# switch.net
KiCad netlist of a schematic drawn in EAGLE
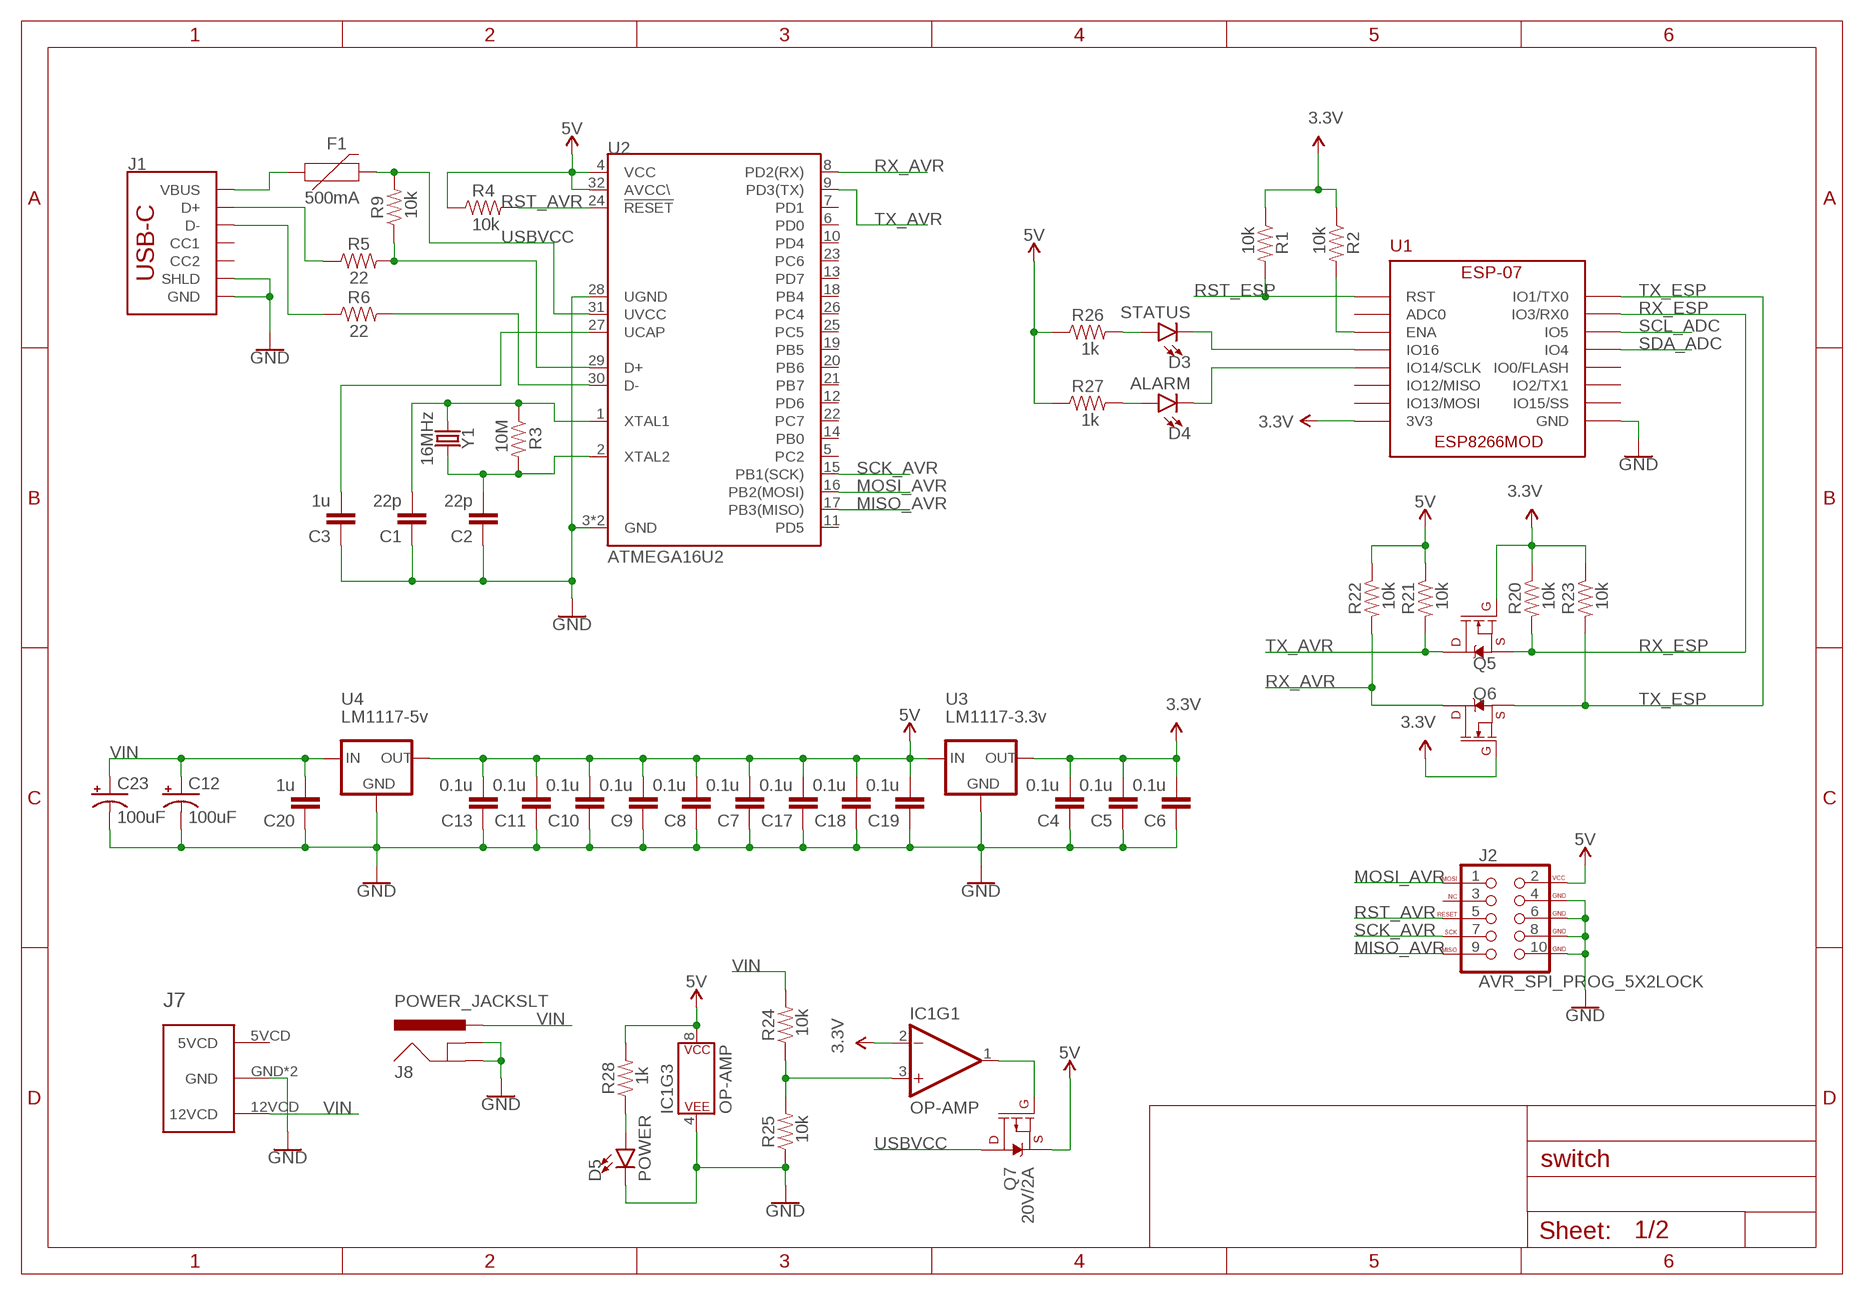
[diagram p0: schematic, sheet 1]
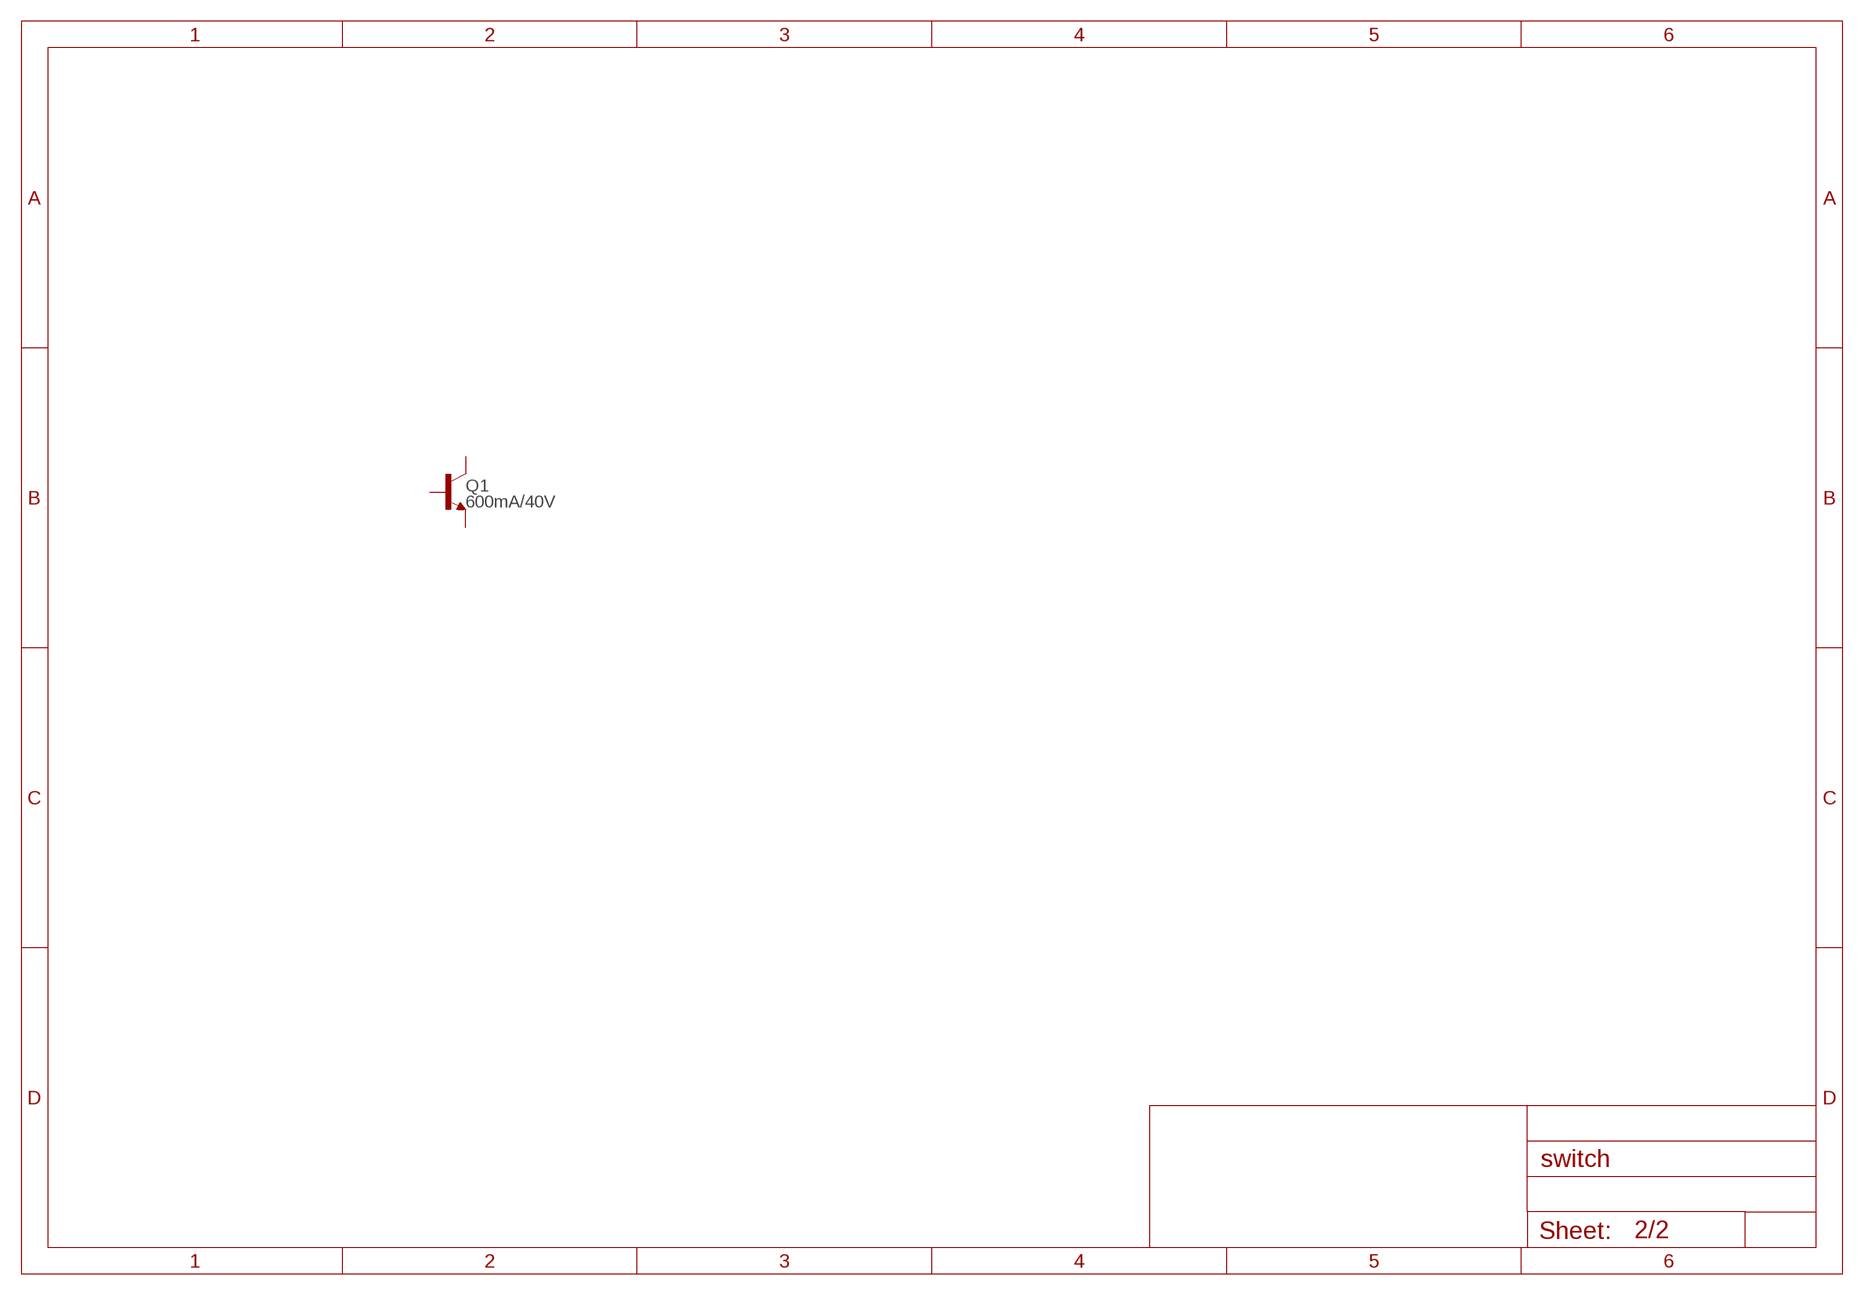
[diagram p1: schematic, sheet 2]

(export (version "E")
  (design (tool "Eeschema 10.0.6"))
  (components
    (comp (ref "C1")
      (value "22p")
      (footprint "eagle-import:0805")
      (libsource (lib "eagle-import") (part "CAP-0805"))
    )
    (comp (ref "C2")
      (value "22p")
      (footprint "eagle-import:0805")
      (libsource (lib "eagle-import") (part "CAP-0805"))
    )
    (comp (ref "C3")
      (value "1u")
      (footprint "eagle-import:0805")
      (libsource (lib "eagle-import") (part "CAP-0805"))
    )
    (comp (ref "C4")
      (value "0.1u")
      (footprint "eagle-import:0805")
      (libsource (lib "eagle-import") (part "CAP-0805"))
    )
    (comp (ref "C5")
      (value "0.1u")
      (footprint "eagle-import:0805")
      (libsource (lib "eagle-import") (part "CAP-0805"))
    )
    (comp (ref "C6")
      (value "0.1u")
      (footprint "eagle-import:0805")
      (libsource (lib "eagle-import") (part "CAP-0805"))
    )
    (comp (ref "C7")
      (value "0.1u")
      (footprint "eagle-import:0805")
      (libsource (lib "eagle-import") (part "CAP-0805"))
    )
    (comp (ref "C8")
      (value "0.1u")
      (footprint "eagle-import:0805")
      (libsource (lib "eagle-import") (part "CAP-0805"))
    )
    (comp (ref "C9")
      (value "0.1u")
      (footprint "eagle-import:0805")
      (libsource (lib "eagle-import") (part "CAP-0805"))
    )
    (comp (ref "C10")
      (value "0.1u")
      (footprint "eagle-import:0805")
      (libsource (lib "eagle-import") (part "CAP-0805"))
    )
    (comp (ref "C11")
      (value "0.1u")
      (footprint "eagle-import:0805")
      (libsource (lib "eagle-import") (part "CAP-0805"))
    )
    (comp (ref "C12")
      (value "100uF")
      (footprint "eagle-import:PANASONIC_D")
      (libsource (lib "eagle-import") (part "100UF-POLAR-25V-20%(ELEC)"))
    )
    (comp (ref "C13")
      (value "0.1u")
      (footprint "eagle-import:0805")
      (libsource (lib "eagle-import") (part "CAP-0805"))
    )
    (comp (ref "C17")
      (value "0.1u")
      (footprint "eagle-import:0805")
      (libsource (lib "eagle-import") (part "CAP-0805"))
    )
    (comp (ref "C18")
      (value "0.1u")
      (footprint "eagle-import:0805")
      (libsource (lib "eagle-import") (part "CAP-0805"))
    )
    (comp (ref "C19")
      (value "0.1u")
      (footprint "eagle-import:0805")
      (libsource (lib "eagle-import") (part "CAP-0805"))
    )
    (comp (ref "C20")
      (value "1u")
      (footprint "eagle-import:0805")
      (libsource (lib "eagle-import") (part "CAP-0805"))
    )
    (comp (ref "C23")
      (value "100uF")
      (footprint "eagle-import:PANASONIC_D")
      (libsource (lib "eagle-import") (part "100UF-POLAR-25V-20%(ELEC)"))
    )
    (comp (ref "D3")
      (value "STATUS")
      (footprint "eagle-import:LED-0603")
      (libsource (lib "eagle-import") (part "LED-YELLOW0603"))
    )
    (comp (ref "D4")
      (value "ALARM")
      (footprint "eagle-import:LED-0603")
      (libsource (lib "eagle-import") (part "LED-YELLOW0603"))
    )
    (comp (ref "D5")
      (value "POWER")
      (footprint "eagle-import:LED-0603")
      (libsource (lib "eagle-import") (part "LED-YELLOW0603"))
    )
    (comp (ref "F1")
      (value "500mA")
      (footprint "eagle-import:1812")
      (libsource (lib "eagle-import") (part "PPTC_16V_2.5A"))
    )
    (comp (ref "IC1")
      (value "OP-AMP")
      (footprint "eagle-import:SO08")
      (libsource (lib "eagle-import") (part "OPAMP-DUALU"))
    )
    (comp (ref "J1")
      (value "USB_C_2-LAYER_PADS")
      (footprint "eagle-import:USB-C-16P-2LAYER-PADS")
      (libsource (lib "eagle-import") (part "USB_C_2-LAYER_PADS"))
    )
    (comp (ref "J2")
      (value "AVR_SPI_PROG_5X2LOCK")
      (footprint "eagle-import:2X5-SHROUDED_LOCK")
      (libsource (lib "eagle-import") (part "AVR_SPI_PROG_5X2LOCK"))
    )
    (comp (ref "J7")
      (value "MOLEX-CPU-POWER")
      (footprint "eagle-import:MOLEX-5.08-4PIN")
      (libsource (lib "eagle-import") (part "MOLEX-CPU-POWER"))
    )
    (comp (ref "J8")
      (value "POWER_JACKSLT")
      (footprint "eagle-import:POWER_JACK_SLOT")
      (libsource (lib "eagle-import") (part "POWER_JACKSLT"))
    )
    (comp (ref "Q5")
      (value "220mA/50V/3.5Ω")
      (footprint "eagle-import:SOT23-3")
      (libsource (lib "eagle-import") (part "MOSFET-NCH-BSS138"))
    )
    (comp (ref "Q6")
      (value "220mA/50V/3.5Ω")
      (footprint "eagle-import:SOT23-3")
      (libsource (lib "eagle-import") (part "MOSFET-NCH-BSS138"))
    )
    (comp (ref "Q7")
      (value "20V/2A")
      (footprint "eagle-import:SOT23-3")
      (libsource (lib "eagle-import") (part "MOSFET_PCH-DMG2305UX-7"))
    )
    (comp (ref "R1")
      (value "10k")
      (footprint "eagle-import:0805")
      (libsource (lib "eagle-import") (part "RESISTOR0805"))
    )
    (comp (ref "R2")
      (value "10k")
      (footprint "eagle-import:0805")
      (libsource (lib "eagle-import") (part "RESISTOR0805"))
    )
    (comp (ref "R3")
      (value "10M")
      (footprint "eagle-import:0805")
      (libsource (lib "eagle-import") (part "RESISTOR0805"))
    )
    (comp (ref "R4")
      (value "10k")
      (footprint "eagle-import:0805")
      (libsource (lib "eagle-import") (part "RESISTOR0805"))
    )
    (comp (ref "R5")
      (value "22")
      (footprint "eagle-import:0805")
      (libsource (lib "eagle-import") (part "RESISTOR0805"))
    )
    (comp (ref "R6")
      (value "22")
      (footprint "eagle-import:0805")
      (libsource (lib "eagle-import") (part "RESISTOR0805"))
    )
    (comp (ref "R9")
      (value "10k")
      (footprint "eagle-import:0805")
      (libsource (lib "eagle-import") (part "RESISTOR0805"))
    )
    (comp (ref "R20")
      (value "10k")
      (footprint "eagle-import:0805")
      (libsource (lib "eagle-import") (part "RESISTOR0805"))
    )
    (comp (ref "R21")
      (value "10k")
      (footprint "eagle-import:0805")
      (libsource (lib "eagle-import") (part "RESISTOR0805"))
    )
    (comp (ref "R22")
      (value "10k")
      (footprint "eagle-import:0805")
      (libsource (lib "eagle-import") (part "RESISTOR0805"))
    )
    (comp (ref "R23")
      (value "10k")
      (footprint "eagle-import:0805")
      (libsource (lib "eagle-import") (part "RESISTOR0805"))
    )
    (comp (ref "R24")
      (value "10k")
      (footprint "eagle-import:0805")
      (libsource (lib "eagle-import") (part "RESISTOR0805"))
    )
    (comp (ref "R25")
      (value "10k")
      (footprint "eagle-import:0805")
      (libsource (lib "eagle-import") (part "RESISTOR0805"))
    )
    (comp (ref "R26")
      (value "1k")
      (footprint "eagle-import:0805")
      (libsource (lib "eagle-import") (part "RESISTOR0805"))
    )
    (comp (ref "R27")
      (value "1k")
      (footprint "eagle-import:0805")
      (libsource (lib "eagle-import") (part "RESISTOR0805"))
    )
    (comp (ref "R28")
      (value "1k")
      (footprint "eagle-import:0805")
      (libsource (lib "eagle-import") (part "RESISTOR0805"))
    )
    (comp (ref "U1")
      (value "ESP-07")
      (footprint "eagle-import:ESP-07")
      (libsource (lib "eagle-import") (part "ESP-07"))
    )
    (comp (ref "U2")
      (value "ATMEGA16U2")
      (footprint "eagle-import:QFN32")
      (libsource (lib "eagle-import") (part "ATMEGA16U2"))
    )
    (comp (ref "U3")
      (value "LM1117-3.3v")
      (footprint "eagle-import:SOT223")
      (libsource (lib "eagle-import") (part "V_REG_LD1117VXXLD1117-SMD"))
    )
    (comp (ref "U4")
      (value "LM1117-5v")
      (footprint "eagle-import:SOT223")
      (libsource (lib "eagle-import") (part "V_REG_LD1117VXXLD1117-SMD"))
    )
    (comp (ref "Y1")
      (value "16MHz")
      (footprint "eagle-import:CRYSTAL-SMD-5X3.2-4PAD")
      (libsource (lib "eagle-import") (part "CRYSTAL-16MHZSMD-5X3.2"))
    )
    (comp (ref "Q1")
      (value "600mA/40V")
      (footprint "eagle-import:SOT23-3")
      (libsource (lib "eagle-import") (part "TRANS_NPN-MMBT2222AL"))
    )
  )
  (nets
    (net (code "1") (name "3.3V") (class "Default")
      (node (ref "C4") (pin "2") (pinfunction "2_2") (pintype "passive"))
      (node (ref "C5") (pin "2") (pinfunction "2_2") (pintype "passive"))
      (node (ref "C6") (pin "2") (pinfunction "2_2") (pintype "passive"))
      (node (ref "IC1") (pin "2") (pinfunction "-IN_2") (pintype "input"))
      (node (ref "Q5") (pin "1") (pinfunction "G_1") (pintype "bidirectional"))
      (node (ref "Q6") (pin "1") (pinfunction "G_1") (pintype "bidirectional"))
      (node (ref "R1") (pin "1") (pinfunction "1_1") (pintype "passive"))
      (node (ref "R2") (pin "1") (pinfunction "1_1") (pintype "passive"))
      (node (ref "R20") (pin "1") (pinfunction "1_1") (pintype "passive"))
      (node (ref "R23") (pin "1") (pinfunction "1_1") (pintype "passive"))
      (node (ref "U1") (pin "3V3") (pinfunction "3V3_3V3") (pintype "power_in"))
      (node (ref "U3") (pin "2") (pinfunction "OUT_2") (pintype "passive"))
    )
    (net (code "2") (name "5V") (class "Default")
      (node (ref "C10") (pin "2") (pinfunction "2_2") (pintype "passive"))
      (node (ref "C11") (pin "2") (pinfunction "2_2") (pintype "passive"))
      (node (ref "C13") (pin "2") (pinfunction "2_2") (pintype "passive"))
      (node (ref "C17") (pin "2") (pinfunction "2_2") (pintype "passive"))
      (node (ref "C18") (pin "2") (pinfunction "2_2") (pintype "passive"))
      (node (ref "C19") (pin "2") (pinfunction "2_2") (pintype "passive"))
      (node (ref "C7") (pin "2") (pinfunction "2_2") (pintype "passive"))
      (node (ref "C8") (pin "2") (pinfunction "2_2") (pintype "passive"))
      (node (ref "C9") (pin "2") (pinfunction "2_2") (pintype "passive"))
      (node (ref "IC1") (pin "8") (pinfunction "P$V+_8") (pintype "bidirectional"))
      (node (ref "J2") (pin "2") (pinfunction "VCC_2") (pintype "power_in"))
      (node (ref "Q7") (pin "2") (pinfunction "S_2") (pintype "bidirectional"))
      (node (ref "R21") (pin "1") (pinfunction "1_1") (pintype "passive"))
      (node (ref "R22") (pin "1") (pinfunction "1_1") (pintype "passive"))
      (node (ref "R26") (pin "1") (pinfunction "1_1") (pintype "passive"))
      (node (ref "R27") (pin "1") (pinfunction "1_1") (pintype "passive"))
      (node (ref "R28") (pin "2") (pinfunction "2_2") (pintype "passive"))
      (node (ref "R4") (pin "1") (pinfunction "1_1") (pintype "passive"))
      (node (ref "U2") (pin "32") (pinfunction "AVCC\\_32") (pintype "bidirectional"))
      (node (ref "U2") (pin "4") (pinfunction "VCC_4") (pintype "bidirectional"))
      (node (ref "U3") (pin "3") (pinfunction "IN_3") (pintype "input"))
      (node (ref "U4") (pin "2") (pinfunction "OUT_2") (pintype "passive"))
    )
    (net (code "3") (name "GND") (class "Default")
      (node (ref "C1") (pin "1") (pinfunction "1_1") (pintype "passive"))
      (node (ref "C10") (pin "1") (pinfunction "1_1") (pintype "passive"))
      (node (ref "C11") (pin "1") (pinfunction "1_1") (pintype "passive"))
      (node (ref "C12") (pin "-") (pinfunction "-_-") (pintype "passive"))
      (node (ref "C13") (pin "1") (pinfunction "1_1") (pintype "passive"))
      (node (ref "C17") (pin "1") (pinfunction "1_1") (pintype "passive"))
      (node (ref "C18") (pin "1") (pinfunction "1_1") (pintype "passive"))
      (node (ref "C19") (pin "1") (pinfunction "1_1") (pintype "passive"))
      (node (ref "C2") (pin "1") (pinfunction "1_1") (pintype "passive"))
      (node (ref "C20") (pin "1") (pinfunction "1_1") (pintype "passive"))
      (node (ref "C23") (pin "-") (pinfunction "-_-") (pintype "passive"))
      (node (ref "C3") (pin "1") (pinfunction "1_1") (pintype "passive"))
      (node (ref "C4") (pin "1") (pinfunction "1_1") (pintype "passive"))
      (node (ref "C5") (pin "1") (pinfunction "1_1") (pintype "passive"))
      (node (ref "C6") (pin "1") (pinfunction "1_1") (pintype "passive"))
      (node (ref "C7") (pin "1") (pinfunction "1_1") (pintype "passive"))
      (node (ref "C8") (pin "1") (pinfunction "1_1") (pintype "passive"))
      (node (ref "C9") (pin "1") (pinfunction "1_1") (pintype "passive"))
      (node (ref "D5") (pin "C") (pinfunction "C_C") (pintype "passive"))
      (node (ref "IC1") (pin "4") (pinfunction "P$V-_4") (pintype "bidirectional"))
      (node (ref "J1") (pin "GND") (pinfunction "GND_GND") (pintype "bidirectional"))
      (node (ref "J1") (pin "GND2") (pinfunction "GND_GND2") (pintype "bidirectional"))
      (node (ref "J1") (pin "SHLD1") (pinfunction "SHLD_SHLD1") (pintype "bidirectional"))
      (node (ref "J1") (pin "SHLD2") (pinfunction "SHLD_SHLD2") (pintype "bidirectional"))
      (node (ref "J1") (pin "SHLD3") (pinfunction "SHLD_SHLD3") (pintype "bidirectional"))
      (node (ref "J1") (pin "SHLD4") (pinfunction "SHLD_SHLD4") (pintype "bidirectional"))
      (node (ref "J2") (pin "10") (pinfunction "GND_10") (pintype "power_in"))
      (node (ref "J2") (pin "4") (pinfunction "GND_4") (pintype "power_in"))
      (node (ref "J2") (pin "6") (pinfunction "GND_6") (pintype "power_in"))
      (node (ref "J2") (pin "8") (pinfunction "GND_8") (pintype "power_in"))
      (node (ref "J7") (pin "GND") (pinfunction "GND_GND") (pintype "bidirectional"))
      (node (ref "J7") (pin "GND2") (pinfunction "GND_GND2") (pintype "bidirectional"))
      (node (ref "J8") (pin "GND@1") (pinfunction "GNDBREAK_GND@1") (pintype "bidirectional"))
      (node (ref "J8") (pin "GND@2") (pinfunction "GND_GND@2") (pintype "bidirectional"))
      (node (ref "R25") (pin "1") (pinfunction "1_1") (pintype "passive"))
      (node (ref "U1") (pin "GND") (pinfunction "GND_GND") (pintype "power_in"))
      (node (ref "U2") (pin "28") (pinfunction "UGND_28") (pintype "bidirectional"))
      (node (ref "U2") (pin "3") (pinfunction "GND_3") (pintype "bidirectional"))
      (node (ref "U2") (pin "EP") (pinfunction "GND_EP") (pintype "bidirectional"))
      (node (ref "U3") (pin "1") (pinfunction "GND_1") (pintype "input"))
      (node (ref "U4") (pin "1") (pinfunction "GND_1") (pintype "input"))
    )
    (net (code "4") (name "MISO_AVR") (class "Default")
      (node (ref "J2") (pin "9") (pinfunction "MISO_9") (pintype "passive"))
      (node (ref "U2") (pin "17") (pinfunction "PB3(MISO)_17") (pintype "bidirectional"))
    )
    (net (code "5") (name "MOSI_AVR") (class "Default")
      (node (ref "J2") (pin "1") (pinfunction "MOSI_1") (pintype "passive"))
      (node (ref "U2") (pin "16") (pinfunction "PB2(MOSI)_16") (pintype "bidirectional"))
    )
    (net (code "6") (name "Net-(D3-PadA)") (class "Default")
      (node (ref "D3") (pin "A") (pinfunction "A_A") (pintype "passive"))
      (node (ref "R26") (pin "2") (pinfunction "2_2") (pintype "passive"))
    )
    (net (code "7") (name "Net-(D4-PadA)") (class "Default")
      (node (ref "D4") (pin "A") (pinfunction "A_A") (pintype "passive"))
      (node (ref "R27") (pin "2") (pinfunction "2_2") (pintype "passive"))
    )
    (net (code "8") (name "Net-(D5-PadA)") (class "Default")
      (node (ref "D5") (pin "A") (pinfunction "A_A") (pintype "passive"))
      (node (ref "R28") (pin "1") (pinfunction "1_1") (pintype "passive"))
    )
    (net (code "9") (name "Net-(F1-Pad1)") (class "Default")
      (node (ref "F1") (pin "1") (pinfunction "1_1") (pintype "bidirectional"))
      (node (ref "J1") (pin "VBUS1") (pinfunction "VBUS_VBUS1") (pintype "bidirectional"))
      (node (ref "J1") (pin "VBUS2") (pinfunction "VBUS_VBUS2") (pintype "bidirectional"))
    )
    (net (code "10") (name "Net-(IC1A-+IN)") (class "Default")
      (node (ref "IC1") (pin "3") (pinfunction "+IN_3") (pintype "input"))
      (node (ref "R24") (pin "1") (pinfunction "1_1") (pintype "passive"))
      (node (ref "R25") (pin "2") (pinfunction "2_2") (pintype "passive"))
    )
    (net (code "11") (name "Net-(IC1A-OUT)") (class "Default")
      (node (ref "IC1") (pin "1") (pinfunction "OUT_1") (pintype "output"))
      (node (ref "Q7") (pin "1") (pinfunction "G_1") (pintype "bidirectional"))
    )
    (net (code "12") (name "Net-(J1-D+-PadA6)") (class "Default")
      (node (ref "J1") (pin "A6") (pinfunction "D+_A6") (pintype "bidirectional"))
      (node (ref "J1") (pin "B6") (pinfunction "D+_B6") (pintype "bidirectional"))
      (node (ref "R5") (pin "1") (pinfunction "1_1") (pintype "passive"))
    )
    (net (code "13") (name "Net-(J1-D--PadA7)") (class "Default")
      (node (ref "J1") (pin "A7") (pinfunction "D-_A7") (pintype "bidirectional"))
      (node (ref "J1") (pin "B7") (pinfunction "D-_B7") (pintype "bidirectional"))
      (node (ref "R6") (pin "1") (pinfunction "1_1") (pintype "passive"))
    )
    (net (code "14") (name "Net-(R2-Pad2)") (class "Default")
      (node (ref "R2") (pin "2") (pinfunction "2_2") (pintype "passive"))
      (node (ref "U1") (pin "ENA") (pinfunction "ENA_ENA") (pintype "input"))
    )
    (net (code "15") (name "Net-(U1-IO14{slash}SCLK)") (class "Default")
      (node (ref "D4") (pin "C") (pinfunction "C_C") (pintype "passive"))
      (node (ref "U1") (pin "IO14") (pinfunction "IO14/SCLK_IO14") (pintype "bidirectional"))
    )
    (net (code "16") (name "Net-(U1-IO16)") (class "Default")
      (node (ref "D3") (pin "C") (pinfunction "C_C") (pintype "passive"))
      (node (ref "U1") (pin "I016") (pinfunction "IO16_I016") (pintype "bidirectional"))
    )
    (net (code "17") (name "Net-(U2-D+)") (class "Default")
      (node (ref "R5") (pin "2") (pinfunction "2_2") (pintype "passive"))
      (node (ref "R9") (pin "1") (pinfunction "1_1") (pintype "passive"))
      (node (ref "U2") (pin "29") (pinfunction "D+_29") (pintype "bidirectional"))
    )
    (net (code "18") (name "Net-(U2-D-)") (class "Default")
      (node (ref "R6") (pin "2") (pinfunction "2_2") (pintype "passive"))
      (node (ref "U2") (pin "30") (pinfunction "D-_30") (pintype "bidirectional"))
    )
    (net (code "19") (name "Net-(U2-UCAP)") (class "Default")
      (node (ref "C3") (pin "2") (pinfunction "2_2") (pintype "passive"))
      (node (ref "U2") (pin "27") (pinfunction "UCAP_27") (pintype "bidirectional"))
    )
    (net (code "20") (name "Net-(U2-XTAL1)") (class "Default")
      (node (ref "C1") (pin "2") (pinfunction "2_2") (pintype "passive"))
      (node (ref "R3") (pin "1") (pinfunction "1_1") (pintype "passive"))
      (node (ref "U2") (pin "1") (pinfunction "XTAL1_1") (pintype "bidirectional"))
      (node (ref "Y1") (pin "1") (pinfunction "1_1") (pintype "passive"))
    )
    (net (code "21") (name "Net-(U2-XTAL2)") (class "Default")
      (node (ref "C2") (pin "2") (pinfunction "2_2") (pintype "passive"))
      (node (ref "R3") (pin "2") (pinfunction "2_2") (pintype "passive"))
      (node (ref "U2") (pin "2") (pinfunction "XTAL2_2") (pintype "bidirectional"))
      (node (ref "Y1") (pin "3") (pinfunction "2_3") (pintype "passive"))
    )
    (net (code "22") (name "RST_AVR") (class "Default")
      (node (ref "J2") (pin "5") (pinfunction "RESET_5") (pintype "passive"))
      (node (ref "R4") (pin "2") (pinfunction "2_2") (pintype "passive"))
      (node (ref "U2") (pin "24") (pinfunction "~{RESET}_24") (pintype "bidirectional"))
    )
    (net (code "23") (name "RST_ESP") (class "Default")
      (node (ref "R1") (pin "2") (pinfunction "2_2") (pintype "passive"))
      (node (ref "U1") (pin "RST") (pinfunction "RST_RST") (pintype "input"))
    )
    (net (code "24") (name "RX_AVR") (class "Default")
      (node (ref "Q6") (pin "3") (pinfunction "D_3") (pintype "bidirectional"))
      (node (ref "R22") (pin "2") (pinfunction "2_2") (pintype "passive"))
      (node (ref "U2") (pin "8") (pinfunction "PD2(RX)_8") (pintype "bidirectional"))
    )
    (net (code "25") (name "RX_ESP") (class "Default")
      (node (ref "Q5") (pin "2") (pinfunction "S_2") (pintype "bidirectional"))
      (node (ref "R20") (pin "2") (pinfunction "2_2") (pintype "passive"))
      (node (ref "U1") (pin "RX0") (pinfunction "IO3/RX0_RX0") (pintype "bidirectional"))
    )
    (net (code "26") (name "SCK_AVR") (class "Default")
      (node (ref "J2") (pin "7") (pinfunction "SCK_7") (pintype "passive"))
      (node (ref "U2") (pin "15") (pinfunction "PB1(SCK)_15") (pintype "bidirectional"))
    )
    (net (code "27") (name "SCL_ADC") (class "Default")
      (node (ref "U1") (pin "IO5") (pinfunction "IO5_IO5") (pintype "bidirectional"))
    )
    (net (code "28") (name "SDA_ADC") (class "Default")
      (node (ref "U1") (pin "IO4") (pinfunction "IO4_IO4") (pintype "bidirectional"))
    )
    (net (code "29") (name "TX_AVR") (class "Default")
      (node (ref "Q5") (pin "3") (pinfunction "D_3") (pintype "bidirectional"))
      (node (ref "R21") (pin "2") (pinfunction "2_2") (pintype "passive"))
      (node (ref "U2") (pin "9") (pinfunction "PD3(TX)_9") (pintype "bidirectional"))
    )
    (net (code "30") (name "TX_ESP") (class "Default")
      (node (ref "Q6") (pin "2") (pinfunction "S_2") (pintype "bidirectional"))
      (node (ref "R23") (pin "2") (pinfunction "2_2") (pintype "passive"))
      (node (ref "U1") (pin "TX0") (pinfunction "IO1/TX0_TX0") (pintype "bidirectional"))
    )
    (net (code "31") (name "USBVCC") (class "Default")
      (node (ref "F1") (pin "2") (pinfunction "2_2") (pintype "bidirectional"))
      (node (ref "Q7") (pin "3") (pinfunction "D_3") (pintype "bidirectional"))
      (node (ref "R9") (pin "2") (pinfunction "2_2") (pintype "passive"))
      (node (ref "U2") (pin "31") (pinfunction "UVCC_31") (pintype "bidirectional"))
    )
    (net (code "32") (name "VIN") (class "Default")
      (node (ref "C12") (pin "+") (pinfunction "+_+") (pintype "passive"))
      (node (ref "C20") (pin "2") (pinfunction "2_2") (pintype "passive"))
      (node (ref "C23") (pin "+") (pinfunction "+_+") (pintype "passive"))
      (node (ref "J7") (pin "12VCD") (pinfunction "12VCD_12VCD") (pintype "bidirectional"))
      (node (ref "J8") (pin "PWR") (pinfunction "PWR_PWR") (pintype "bidirectional"))
      (node (ref "R24") (pin "2") (pinfunction "2_2") (pintype "passive"))
      (node (ref "U4") (pin "3") (pinfunction "IN_3") (pintype "input"))
    )
    (net (code "33") (name "unconnected-(J1-CC1-PadA5)") (class "Default")
      (node (ref "J1") (pin "A5") (pinfunction "CC1_A5") (pintype "bidirectional"))
    )
    (net (code "34") (name "unconnected-(J1-CC2-PadB5)") (class "Default")
      (node (ref "J1") (pin "B5") (pinfunction "CC2_B5") (pintype "bidirectional"))
    )
    (net (code "35") (name "unconnected-(J2-NC-Pad3)") (class "Default")
      (node (ref "J2") (pin "3") (pinfunction "NC_3") (pintype "no_connect"))
    )
    (net (code "36") (name "unconnected-(J7-Pad5VCD)") (class "Default")
      (node (ref "J7") (pin "5VCD") (pinfunction "5VCD_5VCD") (pintype "bidirectional"))
    )
    (net (code "37") (name "unconnected-(Q1-B-Pad1)") (class "Default")
      (node (ref "Q1") (pin "1") (pinfunction "B_1") (pintype "passive"))
    )
    (net (code "38") (name "unconnected-(Q1-C-Pad3)") (class "Default")
      (node (ref "Q1") (pin "3") (pinfunction "C_3") (pintype "passive"))
    )
    (net (code "39") (name "unconnected-(Q1-E-Pad2)") (class "Default")
      (node (ref "Q1") (pin "2") (pinfunction "E_2") (pintype "passive"))
    )
    (net (code "40") (name "unconnected-(U1-ADC0-PadADC)") (class "Default")
      (node (ref "U1") (pin "ADC") (pinfunction "ADC0_ADC") (pintype "input"))
    )
    (net (code "41") (name "unconnected-(U1-IO0{slash}FLASH-PadIO0)") (class "Default")
      (node (ref "U1") (pin "IO0") (pinfunction "IO0/FLASH_IO0") (pintype "bidirectional"))
    )
    (net (code "42") (name "unconnected-(U1-IO2{slash}TX1-PadIO2)") (class "Default")
      (node (ref "U1") (pin "IO2") (pinfunction "IO2/TX1_IO2") (pintype "bidirectional"))
    )
    (net (code "43") (name "unconnected-(U1-IO12{slash}MISO-PadIO12)") (class "Default")
      (node (ref "U1") (pin "IO12") (pinfunction "IO12/MISO_IO12") (pintype "bidirectional"))
    )
    (net (code "44") (name "unconnected-(U1-IO13{slash}MOSI-PadIO13)") (class "Default")
      (node (ref "U1") (pin "IO13") (pinfunction "IO13/MOSI_IO13") (pintype "bidirectional"))
    )
    (net (code "45") (name "unconnected-(U1-IO15{slash}SS-PadIO15)") (class "Default")
      (node (ref "U1") (pin "IO15") (pinfunction "IO15/SS_IO15") (pintype "bidirectional"))
    )
    (net (code "46") (name "unconnected-(U2-PB0-Pad14)") (class "Default")
      (node (ref "U2") (pin "14") (pinfunction "PB0_14") (pintype "bidirectional"))
    )
    (net (code "47") (name "unconnected-(U2-PB4-Pad18)") (class "Default")
      (node (ref "U2") (pin "18") (pinfunction "PB4_18") (pintype "bidirectional"))
    )
    (net (code "48") (name "unconnected-(U2-PB5-Pad19)") (class "Default")
      (node (ref "U2") (pin "19") (pinfunction "PB5_19") (pintype "bidirectional"))
    )
    (net (code "49") (name "unconnected-(U2-PB6-Pad20)") (class "Default")
      (node (ref "U2") (pin "20") (pinfunction "PB6_20") (pintype "bidirectional"))
    )
    (net (code "50") (name "unconnected-(U2-PB7-Pad21)") (class "Default")
      (node (ref "U2") (pin "21") (pinfunction "PB7_21") (pintype "bidirectional"))
    )
    (net (code "51") (name "unconnected-(U2-PC2-Pad5)") (class "Default")
      (node (ref "U2") (pin "5") (pinfunction "PC2_5") (pintype "bidirectional"))
    )
    (net (code "52") (name "unconnected-(U2-PC4-Pad26)") (class "Default")
      (node (ref "U2") (pin "26") (pinfunction "PC4_26") (pintype "bidirectional"))
    )
    (net (code "53") (name "unconnected-(U2-PC5-Pad25)") (class "Default")
      (node (ref "U2") (pin "25") (pinfunction "PC5_25") (pintype "bidirectional"))
    )
    (net (code "54") (name "unconnected-(U2-PC6-Pad23)") (class "Default")
      (node (ref "U2") (pin "23") (pinfunction "PC6_23") (pintype "bidirectional"))
    )
    (net (code "55") (name "unconnected-(U2-PC7-Pad22)") (class "Default")
      (node (ref "U2") (pin "22") (pinfunction "PC7_22") (pintype "bidirectional"))
    )
    (net (code "56") (name "unconnected-(U2-PD0-Pad6)") (class "Default")
      (node (ref "U2") (pin "6") (pinfunction "PD0_6") (pintype "bidirectional"))
    )
    (net (code "57") (name "unconnected-(U2-PD1-Pad7)") (class "Default")
      (node (ref "U2") (pin "7") (pinfunction "PD1_7") (pintype "bidirectional"))
    )
    (net (code "58") (name "unconnected-(U2-PD4-Pad10)") (class "Default")
      (node (ref "U2") (pin "10") (pinfunction "PD4_10") (pintype "bidirectional"))
    )
    (net (code "59") (name "unconnected-(U2-PD5-Pad11)") (class "Default")
      (node (ref "U2") (pin "11") (pinfunction "PD5_11") (pintype "bidirectional"))
    )
    (net (code "60") (name "unconnected-(U2-PD6-Pad12)") (class "Default")
      (node (ref "U2") (pin "12") (pinfunction "PD6_12") (pintype "bidirectional"))
    )
    (net (code "61") (name "unconnected-(U2-PD7-Pad13)") (class "Default")
      (node (ref "U2") (pin "13") (pinfunction "PD7_13") (pintype "bidirectional"))
    )
  )
)
